# DACCACCHE_ERRARD_Schematic-p.net
KiCad netlist of a schematic drawn in EAGLE
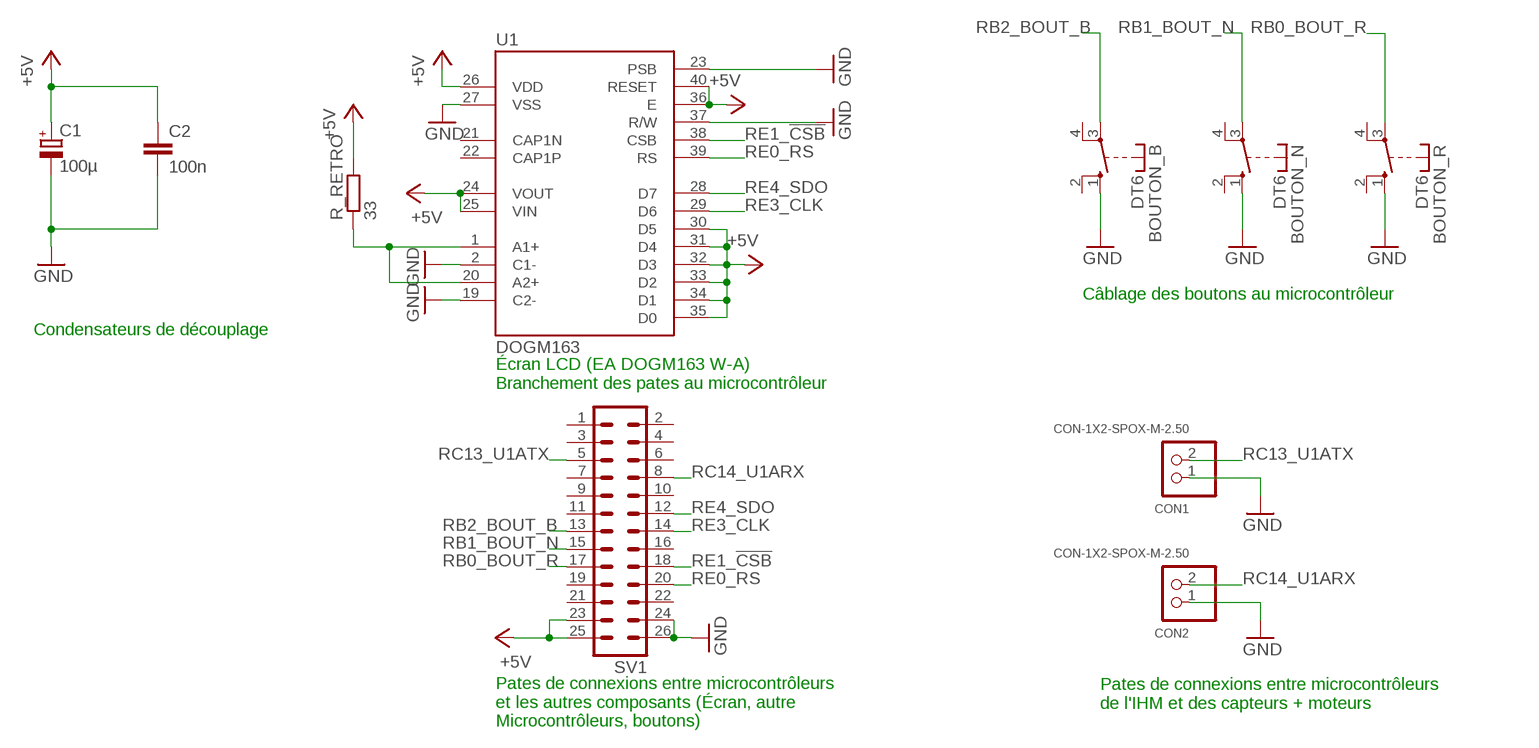
[diagram p0: schematic, sheet 1]

(export (version "E")
  (design (tool "Eeschema 10.0.6"))
  (components
    (comp (ref "BOUTON_B")
      (value "DT6")
      (footprint "eagle-import:DT6")
      (libsource (lib "eagle-import") (part "DT6"))
    )
    (comp (ref "BOUTON_N")
      (value "DT6")
      (footprint "eagle-import:DT6")
      (libsource (lib "eagle-import") (part "DT6"))
    )
    (comp (ref "BOUTON_R")
      (value "DT6")
      (footprint "eagle-import:DT6")
      (libsource (lib "eagle-import") (part "DT6"))
    )
    (comp (ref "C1")
      (value "100µ")
      (footprint "eagle-import:E2,5-7")
      (libsource (lib "eagle-import") (part "CPOL-EUE2.5-7"))
    )
    (comp (ref "C2")
      (value "100n")
      (footprint "eagle-import:C050-030X075")
      (libsource (lib "eagle-import") (part "C-EU050-030X075"))
    )
    (comp (ref "CON1")
      (value "CON-1X2-SPOX-M-2.50")
      (footprint "eagle-import:SPOX-M-2.50-02")
      (libsource (lib "eagle-import") (part "CON-1X2-SPOX-M-2.50"))
    )
    (comp (ref "CON2")
      (value "CON-1X2-SPOX-M-2.50")
      (footprint "eagle-import:SPOX-M-2.50-02")
      (libsource (lib "eagle-import") (part "CON-1X2-SPOX-M-2.50"))
    )
    (comp (ref "R_RETRO")
      (value "33")
      (footprint "eagle-import:0207_10")
      (libsource (lib "eagle-import") (part "R-EU_0207/10"))
    )
    (comp (ref "SV1")
      (value "ML26")
      (footprint "eagle-import:ML26")
      (libsource (lib "eagle-import") (part "ML26"))
    )
    (comp (ref "U1")
      (value "DOGM163")
      (footprint "eagle-import:DOGM")
      (libsource (lib "eagle-import") (part "DOGM163"))
    )
  )
  (nets
    (net (code "1") (name "+5V") (class "Default")
      (node (ref "C1") (pin "+") (pinfunction "+_+") (pintype "passive"))
      (node (ref "C2") (pin "1") (pinfunction "1_1") (pintype "passive"))
      (node (ref "R_RETRO") (pin "2") (pinfunction "2_2") (pintype "passive"))
      (node (ref "SV1") (pin "23") (pinfunction "23_23") (pintype "passive"))
      (node (ref "SV1") (pin "25") (pinfunction "25_25") (pintype "passive"))
      (node (ref "U1") (pin "24") (pinfunction "VOUT_24") (pintype "bidirectional"))
      (node (ref "U1") (pin "25") (pinfunction "VIN_25") (pintype "bidirectional"))
      (node (ref "U1") (pin "26") (pinfunction "VDD_26") (pintype "bidirectional"))
      (node (ref "U1") (pin "30") (pinfunction "D5_30") (pintype "bidirectional"))
      (node (ref "U1") (pin "31") (pinfunction "D4_31") (pintype "bidirectional"))
      (node (ref "U1") (pin "32") (pinfunction "D3_32") (pintype "bidirectional"))
      (node (ref "U1") (pin "33") (pinfunction "D2_33") (pintype "bidirectional"))
      (node (ref "U1") (pin "34") (pinfunction "D1_34") (pintype "bidirectional"))
      (node (ref "U1") (pin "35") (pinfunction "D0_35") (pintype "bidirectional"))
      (node (ref "U1") (pin "36") (pinfunction "E_36") (pintype "bidirectional"))
      (node (ref "U1") (pin "40") (pinfunction "RESET_40") (pintype "bidirectional"))
    )
    (net (code "2") (name "/RB0_BOUT_R") (class "Default")
      (node (ref "BOUTON_R") (pin "3") (pinfunction "P_3") (pintype "passive"))
      (node (ref "SV1") (pin "17") (pinfunction "17_17") (pintype "passive"))
    )
    (net (code "3") (name "/RB1_BOUT_N") (class "Default")
      (node (ref "BOUTON_N") (pin "3") (pinfunction "P_3") (pintype "passive"))
      (node (ref "SV1") (pin "15") (pinfunction "15_15") (pintype "passive"))
    )
    (net (code "4") (name "/RB2_BOUT_B") (class "Default")
      (node (ref "BOUTON_B") (pin "3") (pinfunction "P_3") (pintype "passive"))
      (node (ref "SV1") (pin "13") (pinfunction "13_13") (pintype "passive"))
    )
    (net (code "5") (name "/RC13_U1ATX") (class "Default")
      (node (ref "CON1") (pin "2") (pinfunction "2_2") (pintype "passive"))
      (node (ref "SV1") (pin "5") (pinfunction "5_5") (pintype "passive"))
    )
    (net (code "6") (name "/RC14_U1ARX") (class "Default")
      (node (ref "CON2") (pin "2") (pinfunction "2_2") (pintype "passive"))
      (node (ref "SV1") (pin "8") (pinfunction "8_8") (pintype "passive"))
    )
    (net (code "7") (name "/RE0_RS") (class "Default")
      (node (ref "SV1") (pin "20") (pinfunction "20_20") (pintype "passive"))
      (node (ref "U1") (pin "39") (pinfunction "RS_39") (pintype "bidirectional"))
    )
    (net (code "8") (name "/RE1_~{CSB}") (class "Default")
      (node (ref "SV1") (pin "18") (pinfunction "18_18") (pintype "passive"))
      (node (ref "U1") (pin "38") (pinfunction "CSB_38") (pintype "bidirectional"))
    )
    (net (code "9") (name "/RE3_CLK") (class "Default")
      (node (ref "SV1") (pin "14") (pinfunction "14_14") (pintype "passive"))
      (node (ref "U1") (pin "29") (pinfunction "D6_29") (pintype "bidirectional"))
    )
    (net (code "10") (name "/RE4_SDO") (class "Default")
      (node (ref "SV1") (pin "12") (pinfunction "12_12") (pintype "passive"))
      (node (ref "U1") (pin "28") (pinfunction "D7_28") (pintype "bidirectional"))
    )
    (net (code "11") (name "GND") (class "Default")
      (node (ref "BOUTON_B") (pin "1") (pinfunction "S_1") (pintype "passive"))
      (node (ref "BOUTON_N") (pin "1") (pinfunction "S_1") (pintype "passive"))
      (node (ref "BOUTON_R") (pin "1") (pinfunction "S_1") (pintype "passive"))
      (node (ref "C1") (pin "-") (pinfunction "-_-") (pintype "passive"))
      (node (ref "C2") (pin "2") (pinfunction "2_2") (pintype "passive"))
      (node (ref "CON1") (pin "1") (pinfunction "1_1") (pintype "passive"))
      (node (ref "CON2") (pin "1") (pinfunction "1_1") (pintype "passive"))
      (node (ref "SV1") (pin "24") (pinfunction "24_24") (pintype "passive"))
      (node (ref "SV1") (pin "26") (pinfunction "26_26") (pintype "passive"))
      (node (ref "U1") (pin "19") (pinfunction "C2-_19") (pintype "bidirectional"))
      (node (ref "U1") (pin "2") (pinfunction "C1-_2") (pintype "bidirectional"))
      (node (ref "U1") (pin "23") (pinfunction "PSB_23") (pintype "bidirectional"))
      (node (ref "U1") (pin "27") (pinfunction "VSS_27") (pintype "bidirectional"))
      (node (ref "U1") (pin "37") (pinfunction "R/W_37") (pintype "bidirectional"))
    )
    (net (code "12") (name "Net-(U1-A1+)") (class "Default")
      (node (ref "R_RETRO") (pin "1") (pinfunction "1_1") (pintype "passive"))
      (node (ref "U1") (pin "1") (pinfunction "A1+_1") (pintype "bidirectional"))
      (node (ref "U1") (pin "20") (pinfunction "A2+_20") (pintype "bidirectional"))
    )
    (net (code "13") (name "unconnected-(BOUTON_B-P-Pad4)") (class "Default")
      (node (ref "BOUTON_B") (pin "4") (pinfunction "P_4") (pintype "passive"))
    )
    (net (code "14") (name "unconnected-(BOUTON_B-S-Pad2)") (class "Default")
      (node (ref "BOUTON_B") (pin "2") (pinfunction "S_2") (pintype "passive"))
    )
    (net (code "15") (name "unconnected-(BOUTON_N-P-Pad4)") (class "Default")
      (node (ref "BOUTON_N") (pin "4") (pinfunction "P_4") (pintype "passive"))
    )
    (net (code "16") (name "unconnected-(BOUTON_N-S-Pad2)") (class "Default")
      (node (ref "BOUTON_N") (pin "2") (pinfunction "S_2") (pintype "passive"))
    )
    (net (code "17") (name "unconnected-(BOUTON_R-P-Pad4)") (class "Default")
      (node (ref "BOUTON_R") (pin "4") (pinfunction "P_4") (pintype "passive"))
    )
    (net (code "18") (name "unconnected-(BOUTON_R-S-Pad2)") (class "Default")
      (node (ref "BOUTON_R") (pin "2") (pinfunction "S_2") (pintype "passive"))
    )
    (net (code "19") (name "unconnected-(SV1-Pad1)") (class "Default")
      (node (ref "SV1") (pin "1") (pinfunction "1_1") (pintype "passive"))
    )
    (net (code "20") (name "unconnected-(SV1-Pad2)") (class "Default")
      (node (ref "SV1") (pin "2") (pinfunction "2_2") (pintype "passive"))
    )
    (net (code "21") (name "unconnected-(SV1-Pad3)") (class "Default")
      (node (ref "SV1") (pin "3") (pinfunction "3_3") (pintype "passive"))
    )
    (net (code "22") (name "unconnected-(SV1-Pad4)") (class "Default")
      (node (ref "SV1") (pin "4") (pinfunction "4_4") (pintype "passive"))
    )
    (net (code "23") (name "unconnected-(SV1-Pad6)") (class "Default")
      (node (ref "SV1") (pin "6") (pinfunction "6_6") (pintype "passive"))
    )
    (net (code "24") (name "unconnected-(SV1-Pad7)") (class "Default")
      (node (ref "SV1") (pin "7") (pinfunction "7_7") (pintype "passive"))
    )
    (net (code "25") (name "unconnected-(SV1-Pad9)") (class "Default")
      (node (ref "SV1") (pin "9") (pinfunction "9_9") (pintype "passive"))
    )
    (net (code "26") (name "unconnected-(SV1-Pad10)") (class "Default")
      (node (ref "SV1") (pin "10") (pinfunction "10_10") (pintype "passive"))
    )
    (net (code "27") (name "unconnected-(SV1-Pad11)") (class "Default")
      (node (ref "SV1") (pin "11") (pinfunction "11_11") (pintype "passive"))
    )
    (net (code "28") (name "unconnected-(SV1-Pad16)") (class "Default")
      (node (ref "SV1") (pin "16") (pinfunction "16_16") (pintype "passive"))
    )
    (net (code "29") (name "unconnected-(SV1-Pad19)") (class "Default")
      (node (ref "SV1") (pin "19") (pinfunction "19_19") (pintype "passive"))
    )
    (net (code "30") (name "unconnected-(SV1-Pad21)") (class "Default")
      (node (ref "SV1") (pin "21") (pinfunction "21_21") (pintype "passive"))
    )
    (net (code "31") (name "unconnected-(SV1-Pad22)") (class "Default")
      (node (ref "SV1") (pin "22") (pinfunction "22_22") (pintype "passive"))
    )
    (net (code "32") (name "unconnected-(U1-CAP1N-Pad21)") (class "Default")
      (node (ref "U1") (pin "21") (pinfunction "CAP1N_21") (pintype "bidirectional"))
    )
    (net (code "33") (name "unconnected-(U1-CAP1P-Pad22)") (class "Default")
      (node (ref "U1") (pin "22") (pinfunction "CAP1P_22") (pintype "bidirectional"))
    )
  )
)
